# lcd_1602.net
KiCad netlist of a schematic drawn in EAGLE
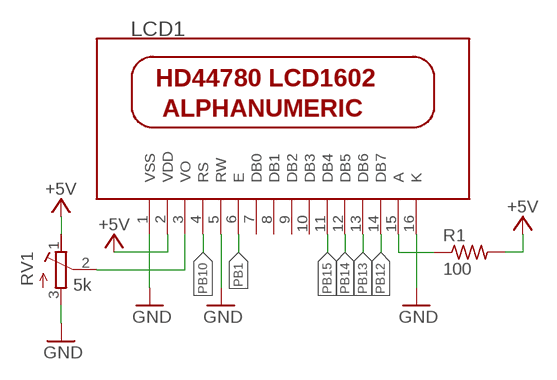
[diagram p0: schematic, sheet 1]

(export (version "E")
  (design (tool "Eeschema 10.0.6"))
  (components
    (comp (ref "LCD1")
      (value "LCD-1602")
      (footprint "eagle-import:LCD-1602")
      (libsource (lib "eagle-import") (part "LCD-1602"))
    )
    (comp (ref "R1")
      (value "100")
      (footprint "eagle-import:R0805")
      (libsource (lib "eagle-import") (part "RESISTOR_R0805"))
    )
    (comp (ref "RV1")
      (value "5k")
      (footprint "eagle-import:TRIMMER_ACOSTADO")
      (libsource (lib "eagle-import") (part "RES-TRIM"))
    )
  )
  (nets
    (net (code "1") (name "+5V") (class "Default")
      (node (ref "LCD1") (pin "2") (pinfunction "VDD_2") (pintype "power_in"))
      (node (ref "R1") (pin "2") (pinfunction "2_2") (pintype "passive"))
      (node (ref "RV1") (pin "1") (pinfunction "E_1") (pintype "passive"))
    )
    (net (code "2") (name "GND") (class "Default")
      (node (ref "LCD1") (pin "1") (pinfunction "VSS_1") (pintype "power_in"))
      (node (ref "LCD1") (pin "16") (pinfunction "K_16") (pintype "input"))
      (node (ref "LCD1") (pin "5") (pinfunction "RW_5") (pintype "input"))
      (node (ref "RV1") (pin "3") (pinfunction "A_3") (pintype "passive"))
    )
    (net (code "3") (name "Net-(LCD1-A)") (class "Default")
      (node (ref "LCD1") (pin "15") (pinfunction "A_15") (pintype "input"))
      (node (ref "R1") (pin "1") (pinfunction "1_1") (pintype "passive"))
    )
    (net (code "4") (name "Net-(LCD1-VO)") (class "Default")
      (node (ref "LCD1") (pin "3") (pinfunction "VO_3") (pintype "input"))
      (node (ref "RV1") (pin "2") (pinfunction "S_2") (pintype "passive"))
    )
    (net (code "5") (name "PB1") (class "Default")
      (node (ref "LCD1") (pin "6") (pinfunction "E_6") (pintype "input"))
    )
    (net (code "6") (name "PB10") (class "Default")
      (node (ref "LCD1") (pin "4") (pinfunction "RS_4") (pintype "input"))
    )
    (net (code "7") (name "PB12") (class "Default")
      (node (ref "LCD1") (pin "14") (pinfunction "DB7_14") (pintype "bidirectional"))
    )
    (net (code "8") (name "PB13") (class "Default")
      (node (ref "LCD1") (pin "13") (pinfunction "DB6_13") (pintype "bidirectional"))
    )
    (net (code "9") (name "PB14") (class "Default")
      (node (ref "LCD1") (pin "12") (pinfunction "DB5_12") (pintype "bidirectional"))
    )
    (net (code "10") (name "PB15") (class "Default")
      (node (ref "LCD1") (pin "11") (pinfunction "DB4_11") (pintype "bidirectional"))
    )
    (net (code "11") (name "unconnected-(LCD1-DB0-Pad7)") (class "Default")
      (node (ref "LCD1") (pin "7") (pinfunction "DB0_7") (pintype "bidirectional"))
    )
    (net (code "12") (name "unconnected-(LCD1-DB1-Pad8)") (class "Default")
      (node (ref "LCD1") (pin "8") (pinfunction "DB1_8") (pintype "bidirectional"))
    )
    (net (code "13") (name "unconnected-(LCD1-DB2-Pad9)") (class "Default")
      (node (ref "LCD1") (pin "9") (pinfunction "DB2_9") (pintype "bidirectional"))
    )
    (net (code "14") (name "unconnected-(LCD1-DB3-Pad10)") (class "Default")
      (node (ref "LCD1") (pin "10") (pinfunction "DB3_10") (pintype "bidirectional"))
    )
  )
)
